# SparkFun_AVR_Programming_Adapter_v12.net
KiCad netlist of a schematic drawn in EAGLE
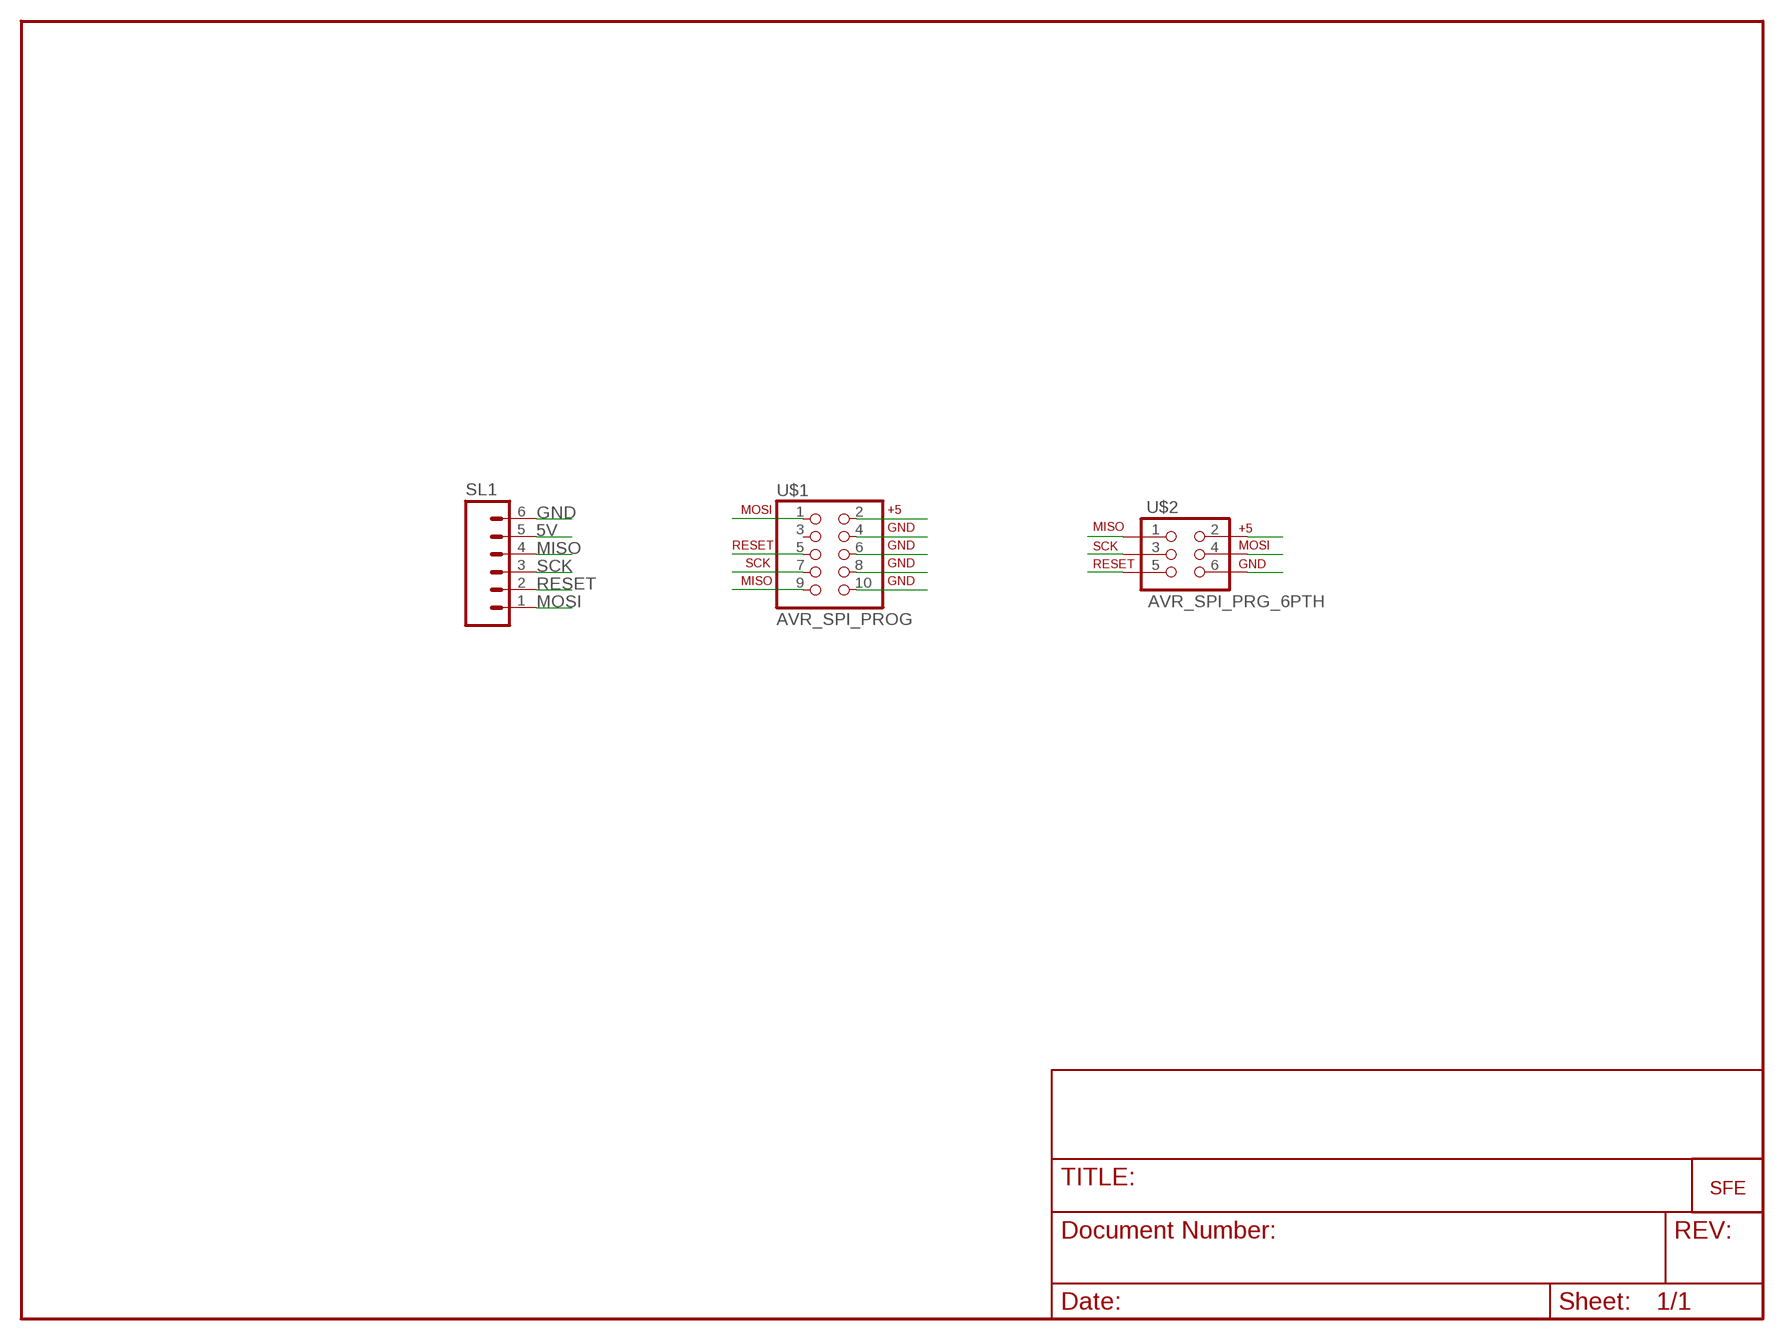
[diagram p0: schematic, sheet 1]

(export (version "E")
  (design (tool "Eeschema 10.0.6"))
  (components
    (comp (ref "SL1")
      (value "M06SIP")
      (footprint "eagle-import:1X06")
      (libsource (lib "eagle-import") (part "M06SIP"))
    )
    (comp (ref "U$1")
      (value "AVR_SPI_PROG")
      (footprint "eagle-import:AVR_ICSP")
      (libsource (lib "eagle-import") (part "AVR_SPI_PROG"))
    )
    (comp (ref "U$2")
      (value "AVR_SPI_PRG_6PTH")
      (footprint "eagle-import:2X3")
      (libsource (lib "eagle-import") (part "AVR_SPI_PRG_6PTH"))
    )
    (comp (ref "U$3")
      (value "LOGO-SFENEW")
      (footprint "eagle-import:SFE-NEW-WEBLOGO")
      (libsource (lib "eagle-import") (part "LOGO-SFENEW"))
    )
  )
  (nets
    (net (code "1") (name "/5V") (class "Default")
      (node (ref "SL1") (pin "5") (pinfunction "5_5") (pintype "passive"))
      (node (ref "U$1") (pin "2") (pinfunction "2_2") (pintype "passive"))
      (node (ref "U$2") (pin "2") (pinfunction "2_2") (pintype "passive"))
    )
    (net (code "2") (name "/GND") (class "Default")
      (node (ref "SL1") (pin "6") (pinfunction "6_6") (pintype "passive"))
      (node (ref "U$1") (pin "10") (pinfunction "10_10") (pintype "passive"))
      (node (ref "U$1") (pin "4") (pinfunction "4_4") (pintype "passive"))
      (node (ref "U$1") (pin "6") (pinfunction "6_6") (pintype "passive"))
      (node (ref "U$1") (pin "8") (pinfunction "8_8") (pintype "passive"))
      (node (ref "U$2") (pin "6") (pinfunction "6_6") (pintype "passive"))
    )
    (net (code "3") (name "/MISO") (class "Default")
      (node (ref "SL1") (pin "4") (pinfunction "4_4") (pintype "passive"))
      (node (ref "U$1") (pin "9") (pinfunction "9_9") (pintype "passive"))
      (node (ref "U$2") (pin "1") (pinfunction "1_1") (pintype "passive"))
    )
    (net (code "4") (name "/MOSI") (class "Default")
      (node (ref "SL1") (pin "1") (pinfunction "1_1") (pintype "passive"))
      (node (ref "U$1") (pin "1") (pinfunction "1_1") (pintype "passive"))
      (node (ref "U$2") (pin "4") (pinfunction "4_4") (pintype "passive"))
    )
    (net (code "5") (name "/RESET") (class "Default")
      (node (ref "SL1") (pin "2") (pinfunction "2_2") (pintype "passive"))
      (node (ref "U$1") (pin "5") (pinfunction "5_5") (pintype "passive"))
      (node (ref "U$2") (pin "5") (pinfunction "5_5") (pintype "passive"))
    )
    (net (code "6") (name "/SCK") (class "Default")
      (node (ref "SL1") (pin "3") (pinfunction "3_3") (pintype "passive"))
      (node (ref "U$1") (pin "7") (pinfunction "7_7") (pintype "passive"))
      (node (ref "U$2") (pin "3") (pinfunction "3_3") (pintype "passive"))
    )
    (net (code "7") (name "unconnected-(U$1-Pad3)") (class "Default")
      (node (ref "U$1") (pin "3") (pinfunction "3_3") (pintype "passive"))
    )
  )
)
